# Kar_IMU.net
KiCad netlist of a schematic drawn in Altium Designer
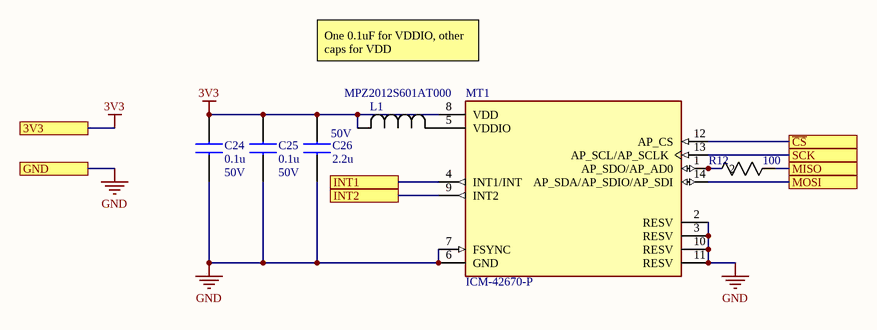
[diagram p0: Kar_IMU.SchDoc]

(export (version "E")
  (design (tool "Eeschema 10.0.6"))
  (components
    (comp (ref "C24")
      (value "0.1u")
      (footprint "CAPC2012X145N")
      (description "Multilayer Ceramic Chip Capacitors, Capacitance=0.1u")
      (fields
        (field (name "MANUFACTURER_PART_NUMBER") "KAM21BR71H104JM")
        (field (name "RATED VOLTAGE") "50V")
      )
      (libsource (lib "Caps") (part "KAM21BR71H104JM"))
    )
    (comp (ref "C25")
      (value "0.1u")
      (footprint "CAPC2012X145N")
      (description "Multilayer Ceramic Chip Capacitors, Capacitance=0.1u")
      (fields
        (field (name "MANUFACTURER_PART_NUMBER") "KAM21BR71H104JM")
        (field (name "RATED VOLTAGE") "50V")
      )
      (libsource (lib "Caps") (part "KAM21BR71H104JM"))
    )
    (comp (ref "C26")
      (value "2.2u")
      (footprint "CAPC2012X145N")
      (description "Multilayer Ceramic Chip Capacitors, Capacitance=2.2u")
      (fields
        (field (name "MANUFACTURER_PART_NUMBER") "C2012X7R1H225K125AE")
        (field (name "RATED VOLTAGE") "50V")
      )
      (libsource (lib "Caps") (part "C2012X7R1H225K125AE"))
    )
    (comp (ref "L1")
      (value "MPZ2012S601AT000")
      (footprint "IND_2012_TDK")
      (description "No Description Available")
      (fields (field (name "COPYRIGHT") "Copyright (C) 2025 Ultra Librarian. All rights reserved."))
      (libsource (lib "MPZ2012S601AT000") (part "MPZ2012S601AT000"))
    )
    (comp (ref "MT1")
      (value "ICM-42670-P")
      (footprint "XDCR_ICM-42670-P")
      (libsource (lib "ICM-42670-P") (part "ICM-42670-P"))
    )
    (comp (ref "R12")
      (value "100")
      (footprint "RC0805N_YAG")
      (description "RES 0805 100 5% 1/8W")
      (fields (field (name "MANUFACTURER_PART_NUMBER") "RC0805JR-07100RL") (field (name "TOLERANCE") "5%"))
      (libsource (lib "Resistors") (part "RC0805JR-07100RL"))
    )
  )
  (nets
    (net (code "1") (name "/INT1") (class "Default")
      (node (ref "MT1") (pin "4") (pinfunction "INT1/INT_4") (pintype "output"))
    )
    (net (code "2") (name "/INT2") (class "Default")
      (node (ref "MT1") (pin "9") (pinfunction "INT2_9") (pintype "output"))
    )
    (net (code "3") (name "/MISO") (class "Default")
      (node (ref "R12") (pin "1") (pinfunction "1_1") (pintype "passive"))
    )
    (net (code "4") (name "/MOSI") (class "Default")
      (node (ref "MT1") (pin "14") (pinfunction "AP_SDA/AP_SDIO/AP_SDI_14") (pintype "bidirectional"))
    )
    (net (code "5") (name "/SCK") (class "Default")
      (node (ref "MT1") (pin "13") (pinfunction "AP_SCL/AP_SCLK_13") (pintype "input"))
    )
    (net (code "6") (name "/~{CS}") (class "Default")
      (node (ref "MT1") (pin "12") (pinfunction "AP_CS_12") (pintype "input"))
    )
    (net (code "7") (name "3V3") (class "Default")
      (node (ref "C24") (pin "2") (pinfunction "2_2") (pintype "passive"))
      (node (ref "C25") (pin "2") (pinfunction "2_2") (pintype "passive"))
      (node (ref "C26") (pin "2") (pinfunction "2_2") (pintype "passive"))
      (node (ref "L1") (pin "2") (pinfunction "2_2") (pintype "passive"))
      (node (ref "MT1") (pin "8") (pinfunction "VDD_8") (pintype "power_in"))
    )
    (net (code "8") (name "GND") (class "Default")
      (node (ref "C24") (pin "1") (pinfunction "1_1") (pintype "passive"))
      (node (ref "C25") (pin "1") (pinfunction "1_1") (pintype "passive"))
      (node (ref "C26") (pin "1") (pinfunction "1_1") (pintype "passive"))
      (node (ref "MT1") (pin "10") (pinfunction "RESV_10") (pintype "passive"))
      (node (ref "MT1") (pin "11") (pinfunction "RESV_11") (pintype "passive"))
      (node (ref "MT1") (pin "2") (pinfunction "RESV_2") (pintype "passive"))
      (node (ref "MT1") (pin "3") (pinfunction "RESV_3") (pintype "passive"))
      (node (ref "MT1") (pin "6") (pinfunction "GND_6") (pintype "power_in"))
      (node (ref "MT1") (pin "7") (pinfunction "FSYNC_7") (pintype "input"))
    )
    (net (code "9") (name "Net-(MT1-AP_SDO{slash}AP_AD0)") (class "Default")
      (node (ref "MT1") (pin "1") (pinfunction "AP_SDO/AP_AD0_1") (pintype "bidirectional"))
      (node (ref "R12") (pin "2") (pinfunction "2_2") (pintype "passive"))
    )
    (net (code "10") (name "Net-(MT1-VDDIO)") (class "Default")
      (node (ref "L1") (pin "1") (pinfunction "1_1") (pintype "passive"))
      (node (ref "MT1") (pin "5") (pinfunction "VDDIO_5") (pintype "power_in"))
    )
  )
)
